# Fuse_Block.net
KiCad netlist of a schematic drawn in Altium Designer
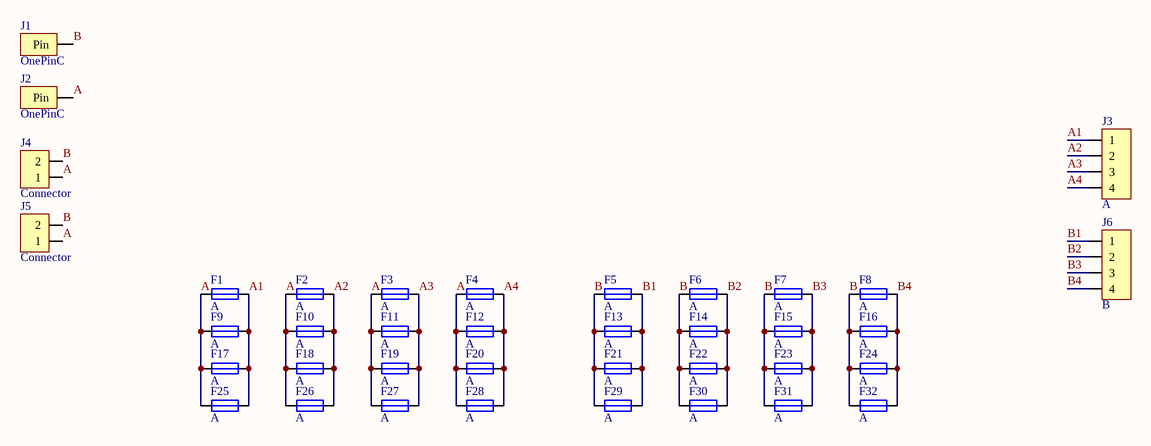
[diagram p0: Fuse Block.SchDoc]

(export (version "E")
  (design (tool "Eeschema 10.0.6"))
  (components
    (comp (ref "F1")
      (value "A")
      (footprint "PassiveComponents:Fuse 9p")
      (description "Round fuse")
      (libsource (lib "PassiveComponents") (part "Fuse"))
    )
    (comp (ref "F2")
      (value "A")
      (footprint "PassiveComponents:Fuse 9p")
      (description "Round fuse")
      (libsource (lib "PassiveComponents") (part "Fuse"))
    )
    (comp (ref "F3")
      (value "A")
      (footprint "PassiveComponents:Fuse 9p")
      (description "Round fuse")
      (libsource (lib "PassiveComponents") (part "Fuse"))
    )
    (comp (ref "F4")
      (value "A")
      (footprint "PassiveComponents:Fuse 9p")
      (description "Round fuse")
      (libsource (lib "PassiveComponents") (part "Fuse"))
    )
    (comp (ref "F5")
      (value "A")
      (footprint "PassiveComponents:Fuse 9p")
      (description "Round fuse")
      (libsource (lib "PassiveComponents") (part "Fuse"))
    )
    (comp (ref "F6")
      (value "A")
      (footprint "PassiveComponents:Fuse 9p")
      (description "Round fuse")
      (libsource (lib "PassiveComponents") (part "Fuse"))
    )
    (comp (ref "F7")
      (value "A")
      (footprint "PassiveComponents:Fuse 9p")
      (description "Round fuse")
      (libsource (lib "PassiveComponents") (part "Fuse"))
    )
    (comp (ref "F8")
      (value "A")
      (footprint "PassiveComponents:Fuse 9p")
      (description "Round fuse")
      (libsource (lib "PassiveComponents") (part "Fuse"))
    )
    (comp (ref "F9")
      (value "A")
      (footprint "PassiveComponents:Fuse Car F 10A")
      (description "Round fuse")
      (libsource (lib "PassiveComponents") (part "Fuse"))
    )
    (comp (ref "F10")
      (value "A")
      (footprint "PassiveComponents:Fuse Car F 10A")
      (description "Round fuse")
      (libsource (lib "PassiveComponents") (part "Fuse"))
    )
    (comp (ref "F11")
      (value "A")
      (footprint "PassiveComponents:Fuse Car F 10A")
      (description "Round fuse")
      (libsource (lib "PassiveComponents") (part "Fuse"))
    )
    (comp (ref "F12")
      (value "A")
      (footprint "PassiveComponents:Fuse Car F 10A")
      (description "Round fuse")
      (libsource (lib "PassiveComponents") (part "Fuse"))
    )
    (comp (ref "F13")
      (value "A")
      (footprint "PassiveComponents:Fuse Car F 10A")
      (description "Round fuse")
      (libsource (lib "PassiveComponents") (part "Fuse"))
    )
    (comp (ref "F14")
      (value "A")
      (footprint "PassiveComponents:Fuse Car F 10A")
      (description "Round fuse")
      (libsource (lib "PassiveComponents") (part "Fuse"))
    )
    (comp (ref "F15")
      (value "A")
      (footprint "PassiveComponents:Fuse Car F 10A")
      (description "Round fuse")
      (libsource (lib "PassiveComponents") (part "Fuse"))
    )
    (comp (ref "F16")
      (value "A")
      (footprint "PassiveComponents:Fuse Car F 10A")
      (description "Round fuse")
      (libsource (lib "PassiveComponents") (part "Fuse"))
    )
    (comp (ref "F17")
      (value "A")
      (footprint "PassiveComponents:Fuse Car Mini")
      (description "Round fuse")
      (libsource (lib "PassiveComponents") (part "Fuse"))
    )
    (comp (ref "F18")
      (value "A")
      (footprint "PassiveComponents:Fuse Car Mini")
      (description "Round fuse")
      (libsource (lib "PassiveComponents") (part "Fuse"))
    )
    (comp (ref "F19")
      (value "A")
      (footprint "PassiveComponents:Fuse Car Mini")
      (description "Round fuse")
      (libsource (lib "PassiveComponents") (part "Fuse"))
    )
    (comp (ref "F20")
      (value "A")
      (footprint "PassiveComponents:Fuse Car Mini")
      (description "Round fuse")
      (libsource (lib "PassiveComponents") (part "Fuse"))
    )
    (comp (ref "F21")
      (value "A")
      (footprint "PassiveComponents:Fuse Car Mini")
      (description "Round fuse")
      (libsource (lib "PassiveComponents") (part "Fuse"))
    )
    (comp (ref "F22")
      (value "A")
      (footprint "PassiveComponents:Fuse Car Mini")
      (description "Round fuse")
      (libsource (lib "PassiveComponents") (part "Fuse"))
    )
    (comp (ref "F23")
      (value "A")
      (footprint "PassiveComponents:Fuse Car Mini")
      (description "Round fuse")
      (libsource (lib "PassiveComponents") (part "Fuse"))
    )
    (comp (ref "F24")
      (value "A")
      (footprint "PassiveComponents:Fuse Car Mini")
      (description "Round fuse")
      (libsource (lib "PassiveComponents") (part "Fuse"))
    )
    (comp (ref "F25")
      (value "A")
      (footprint "PassiveComponents:Fuse 5x20 Open holder")
      (description "Round fuse")
      (libsource (lib "PassiveComponents") (part "Fuse"))
    )
    (comp (ref "F26")
      (value "A")
      (footprint "PassiveComponents:Fuse 5x20 Open holder")
      (description "Round fuse")
      (libsource (lib "PassiveComponents") (part "Fuse"))
    )
    (comp (ref "F27")
      (value "A")
      (footprint "PassiveComponents:Fuse 5x20 Open holder")
      (description "Round fuse")
      (libsource (lib "PassiveComponents") (part "Fuse"))
    )
    (comp (ref "F28")
      (value "A")
      (footprint "PassiveComponents:Fuse 5x20 Open holder")
      (description "Round fuse")
      (libsource (lib "PassiveComponents") (part "Fuse"))
    )
    (comp (ref "F29")
      (value "A")
      (footprint "PassiveComponents:Fuse 5x20 Open holder")
      (description "Round fuse")
      (libsource (lib "PassiveComponents") (part "Fuse"))
    )
    (comp (ref "F30")
      (value "A")
      (footprint "PassiveComponents:Fuse 5x20 Open holder")
      (description "Round fuse")
      (libsource (lib "PassiveComponents") (part "Fuse"))
    )
    (comp (ref "F31")
      (value "A")
      (footprint "PassiveComponents:Fuse 5x20 Open holder")
      (description "Round fuse")
      (libsource (lib "PassiveComponents") (part "Fuse"))
    )
    (comp (ref "F32")
      (value "A")
      (footprint "PassiveComponents:Fuse 5x20 Open holder")
      (description "Round fuse")
      (libsource (lib "PassiveComponents") (part "Fuse"))
    )
    (comp (ref "J1")
      (value "OnePinC")
      (footprint "Connector:OnePin 1.5x4")
      (description "Only pad")
      (libsource (lib "Connector") (part "OnePin Connector"))
    )
    (comp (ref "J2")
      (value "OnePinC")
      (footprint "Connector:OnePin 1.5x4")
      (description "Only pad")
      (libsource (lib "Connector") (part "OnePin Connector"))
    )
    (comp (ref "J3")
      (value "A")
      (footprint "Connector:TBC 7.62 - 4")
      (description "Terminal Block 7.62")
      (libsource (lib "Connector") (part "TBC - 7.62 - 4"))
    )
    (comp (ref "J4")
      (value "Connector")
      (footprint "Connector:DG301 5mm 2p")
      (description "DG301 series")
      (libsource (lib "Connector") (part "DG301-5.0-2P12"))
    )
    (comp (ref "J5")
      (value "Connector")
      (footprint "Connector:TBC 7.62 - 2")
      (description "Terminal Block 7.62")
      (libsource (lib "Connector") (part "TBC - 7.62 - 2"))
    )
    (comp (ref "J6")
      (value "B")
      (footprint "Connector:TBC 7.62 - 4")
      (description "Terminal Block 7.62")
      (libsource (lib "Connector") (part "TBC - 7.62 - 4"))
    )
  )
  (nets
    (net (code "1") (name "/A") (class "Default")
      (node (ref "F1") (pin "1") (pinfunction "1_1") (pintype "passive"))
      (node (ref "F10") (pin "1") (pinfunction "1_1") (pintype "passive"))
      (node (ref "F11") (pin "1") (pinfunction "1_1") (pintype "passive"))
      (node (ref "F12") (pin "1") (pinfunction "1_1") (pintype "passive"))
      (node (ref "F17") (pin "1") (pinfunction "1_1") (pintype "passive"))
      (node (ref "F18") (pin "1") (pinfunction "1_1") (pintype "passive"))
      (node (ref "F19") (pin "1") (pinfunction "1_1") (pintype "passive"))
      (node (ref "F2") (pin "1") (pinfunction "1_1") (pintype "passive"))
      (node (ref "F20") (pin "1") (pinfunction "1_1") (pintype "passive"))
      (node (ref "F25") (pin "1") (pinfunction "1_1") (pintype "passive"))
      (node (ref "F26") (pin "1") (pinfunction "1_1") (pintype "passive"))
      (node (ref "F27") (pin "1") (pinfunction "1_1") (pintype "passive"))
      (node (ref "F28") (pin "1") (pinfunction "1_1") (pintype "passive"))
      (node (ref "F3") (pin "1") (pinfunction "1_1") (pintype "passive"))
      (node (ref "F4") (pin "1") (pinfunction "1_1") (pintype "passive"))
      (node (ref "F9") (pin "1") (pinfunction "1_1") (pintype "passive"))
      (node (ref "J2") (pin "1") (pinfunction "Pin_1") (pintype "passive"))
      (node (ref "J4") (pin "1") (pinfunction "1_1") (pintype "passive"))
      (node (ref "J5") (pin "1") (pinfunction "1_1") (pintype "passive"))
    )
    (net (code "2") (name "/A1") (class "Default")
      (node (ref "F1") (pin "2") (pinfunction "2_2") (pintype "passive"))
      (node (ref "F17") (pin "2") (pinfunction "2_2") (pintype "passive"))
      (node (ref "F25") (pin "2") (pinfunction "2_2") (pintype "passive"))
      (node (ref "F9") (pin "2") (pinfunction "2_2") (pintype "passive"))
      (node (ref "J3") (pin "1") (pinfunction "1_1") (pintype "passive"))
    )
    (net (code "3") (name "/A2") (class "Default")
      (node (ref "F10") (pin "2") (pinfunction "2_2") (pintype "passive"))
      (node (ref "F18") (pin "2") (pinfunction "2_2") (pintype "passive"))
      (node (ref "F2") (pin "2") (pinfunction "2_2") (pintype "passive"))
      (node (ref "F26") (pin "2") (pinfunction "2_2") (pintype "passive"))
      (node (ref "J3") (pin "2") (pinfunction "2_2") (pintype "passive"))
    )
    (net (code "4") (name "/A3") (class "Default")
      (node (ref "F11") (pin "2") (pinfunction "2_2") (pintype "passive"))
      (node (ref "F19") (pin "2") (pinfunction "2_2") (pintype "passive"))
      (node (ref "F27") (pin "2") (pinfunction "2_2") (pintype "passive"))
      (node (ref "F3") (pin "2") (pinfunction "2_2") (pintype "passive"))
      (node (ref "J3") (pin "3") (pinfunction "3_3") (pintype "passive"))
    )
    (net (code "5") (name "/A4") (class "Default")
      (node (ref "F12") (pin "2") (pinfunction "2_2") (pintype "passive"))
      (node (ref "F20") (pin "2") (pinfunction "2_2") (pintype "passive"))
      (node (ref "F28") (pin "2") (pinfunction "2_2") (pintype "passive"))
      (node (ref "F4") (pin "2") (pinfunction "2_2") (pintype "passive"))
      (node (ref "J3") (pin "4") (pinfunction "4_4") (pintype "passive"))
    )
    (net (code "6") (name "/B") (class "Default")
      (node (ref "F13") (pin "1") (pinfunction "1_1") (pintype "passive"))
      (node (ref "F14") (pin "1") (pinfunction "1_1") (pintype "passive"))
      (node (ref "F15") (pin "1") (pinfunction "1_1") (pintype "passive"))
      (node (ref "F16") (pin "1") (pinfunction "1_1") (pintype "passive"))
      (node (ref "F21") (pin "1") (pinfunction "1_1") (pintype "passive"))
      (node (ref "F22") (pin "1") (pinfunction "1_1") (pintype "passive"))
      (node (ref "F23") (pin "1") (pinfunction "1_1") (pintype "passive"))
      (node (ref "F24") (pin "1") (pinfunction "1_1") (pintype "passive"))
      (node (ref "F29") (pin "1") (pinfunction "1_1") (pintype "passive"))
      (node (ref "F30") (pin "1") (pinfunction "1_1") (pintype "passive"))
      (node (ref "F31") (pin "1") (pinfunction "1_1") (pintype "passive"))
      (node (ref "F32") (pin "1") (pinfunction "1_1") (pintype "passive"))
      (node (ref "F5") (pin "1") (pinfunction "1_1") (pintype "passive"))
      (node (ref "F6") (pin "1") (pinfunction "1_1") (pintype "passive"))
      (node (ref "F7") (pin "1") (pinfunction "1_1") (pintype "passive"))
      (node (ref "F8") (pin "1") (pinfunction "1_1") (pintype "passive"))
      (node (ref "J1") (pin "1") (pinfunction "Pin_1") (pintype "passive"))
      (node (ref "J4") (pin "2") (pinfunction "2_2") (pintype "passive"))
      (node (ref "J5") (pin "2") (pinfunction "2_2") (pintype "passive"))
    )
    (net (code "7") (name "/B1") (class "Default")
      (node (ref "F13") (pin "2") (pinfunction "2_2") (pintype "passive"))
      (node (ref "F21") (pin "2") (pinfunction "2_2") (pintype "passive"))
      (node (ref "F29") (pin "2") (pinfunction "2_2") (pintype "passive"))
      (node (ref "F5") (pin "2") (pinfunction "2_2") (pintype "passive"))
      (node (ref "J6") (pin "1") (pinfunction "1_1") (pintype "passive"))
    )
    (net (code "8") (name "/B2") (class "Default")
      (node (ref "F14") (pin "2") (pinfunction "2_2") (pintype "passive"))
      (node (ref "F22") (pin "2") (pinfunction "2_2") (pintype "passive"))
      (node (ref "F30") (pin "2") (pinfunction "2_2") (pintype "passive"))
      (node (ref "F6") (pin "2") (pinfunction "2_2") (pintype "passive"))
      (node (ref "J6") (pin "2") (pinfunction "2_2") (pintype "passive"))
    )
    (net (code "9") (name "/B3") (class "Default")
      (node (ref "F15") (pin "2") (pinfunction "2_2") (pintype "passive"))
      (node (ref "F23") (pin "2") (pinfunction "2_2") (pintype "passive"))
      (node (ref "F31") (pin "2") (pinfunction "2_2") (pintype "passive"))
      (node (ref "F7") (pin "2") (pinfunction "2_2") (pintype "passive"))
      (node (ref "J6") (pin "3") (pinfunction "3_3") (pintype "passive"))
    )
    (net (code "10") (name "/B4") (class "Default")
      (node (ref "F16") (pin "2") (pinfunction "2_2") (pintype "passive"))
      (node (ref "F24") (pin "2") (pinfunction "2_2") (pintype "passive"))
      (node (ref "F32") (pin "2") (pinfunction "2_2") (pintype "passive"))
      (node (ref "F8") (pin "2") (pinfunction "2_2") (pintype "passive"))
      (node (ref "J6") (pin "4") (pinfunction "4_4") (pintype "passive"))
    )
  )
)
